# HG-Badge4.net
KiCad netlist of a schematic drawn in EAGLE
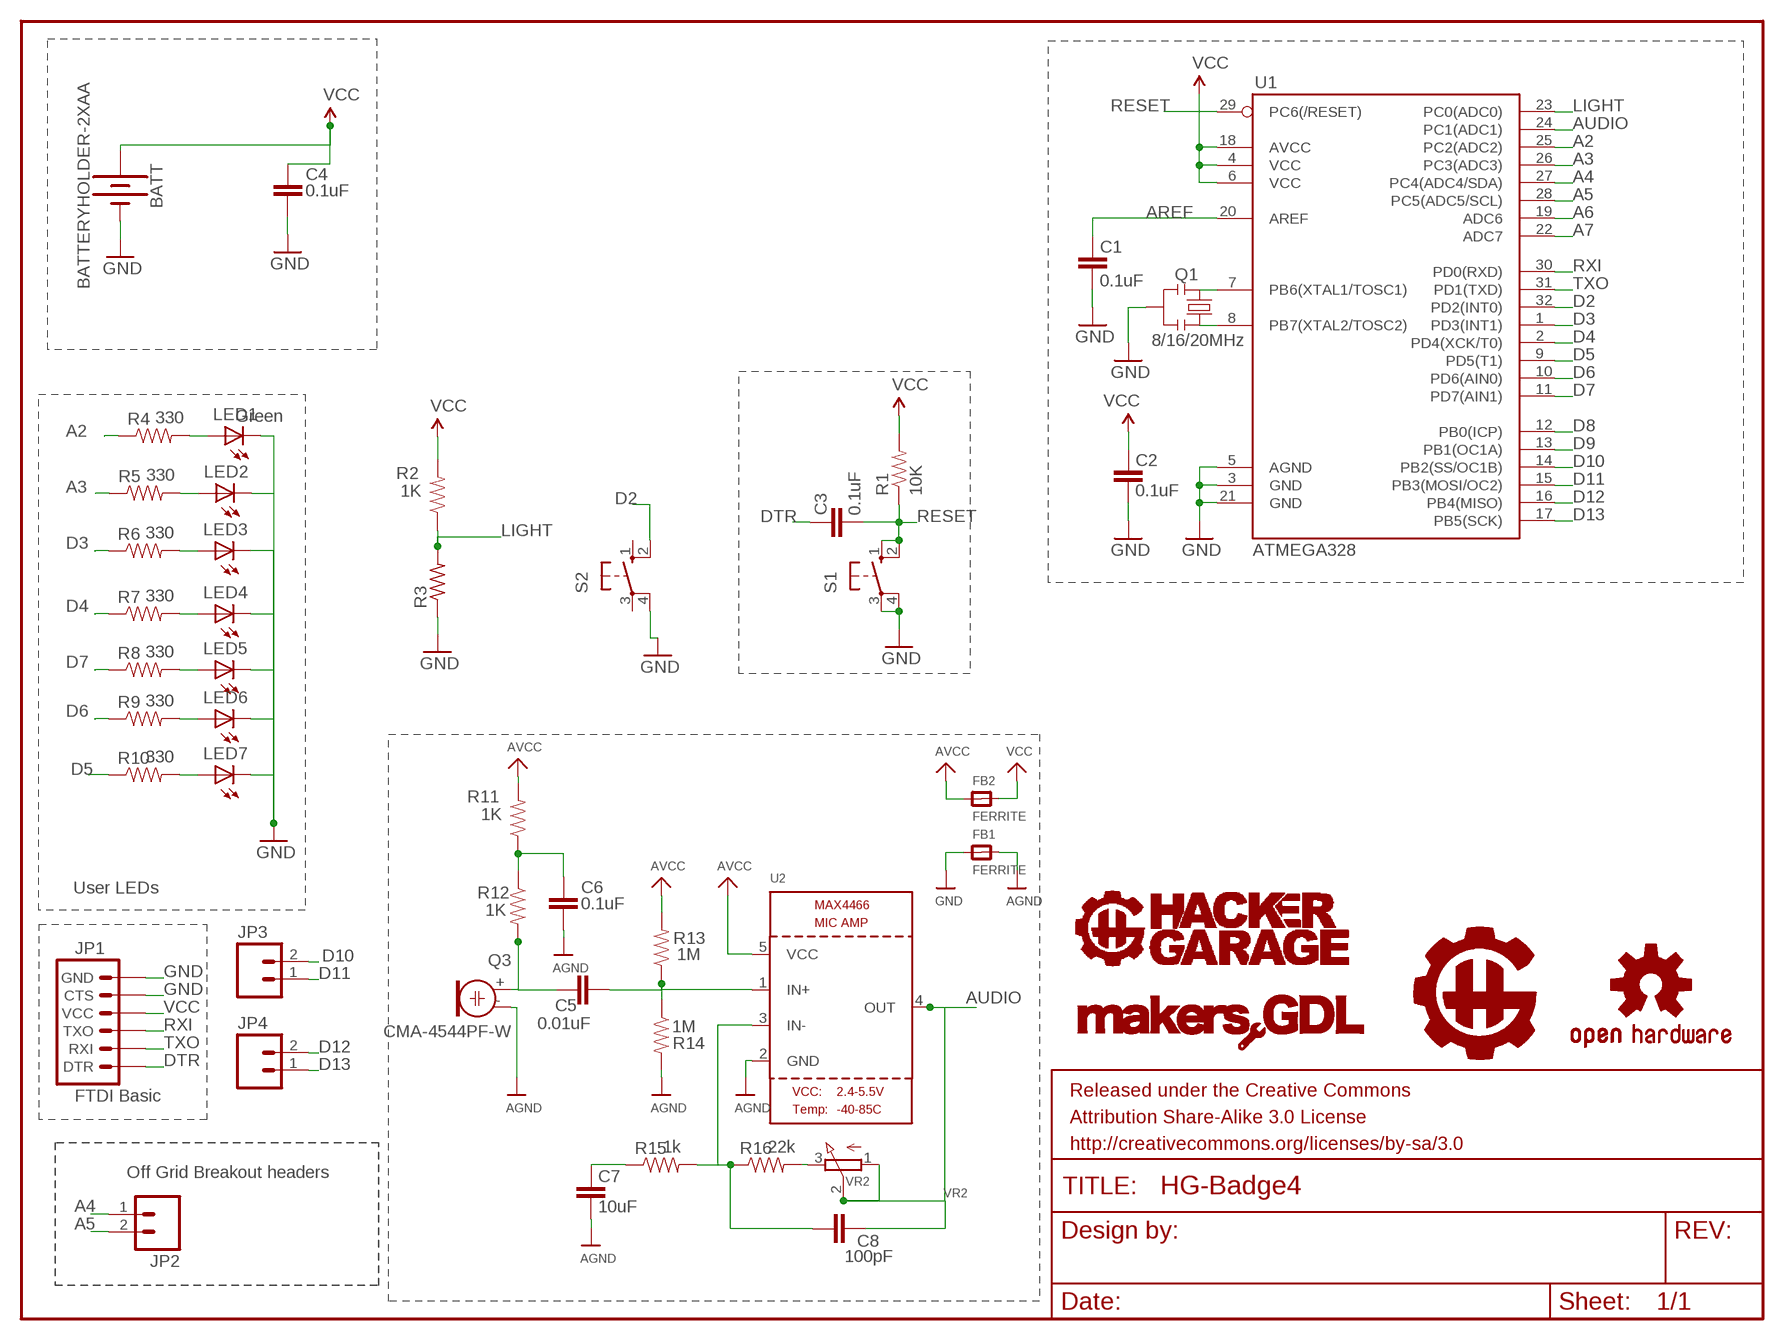
[diagram p0: schematic, sheet 1]

(export (version "E")
  (design (tool "Eeschema 10.0.6"))
  (components
    (comp (ref "BATT")
      (value "BATTERYHOLDER-2XAA")
      (footprint "eagle-import:BATT-HOLDER-2XAAA")
      (libsource (lib "eagle-import") (part "BATTERYHOLDER-2XAA"))
    )
    (comp (ref "C1")
      (value "0.1uF")
      (footprint "eagle-import:0603-CAP")
      (libsource (lib "eagle-import") (part "CAP0603-CAP"))
    )
    (comp (ref "C2")
      (value "0.1uF")
      (footprint "eagle-import:0603-CAP")
      (libsource (lib "eagle-import") (part "CAP0603-CAP"))
    )
    (comp (ref "C3")
      (value "0.1uF")
      (footprint "eagle-import:0603-CAP")
      (libsource (lib "eagle-import") (part "CAP0603-CAP"))
    )
    (comp (ref "C4")
      (value "0.1uF")
      (footprint "eagle-import:0603-CAP")
      (libsource (lib "eagle-import") (part "CAP0603-CAP"))
    )
    (comp (ref "C5")
      (value "0.01uF")
      (footprint "eagle-import:0603-CAP")
      (libsource (lib "eagle-import") (part "CAP0603-CAP"))
    )
    (comp (ref "C6")
      (value "0.1uF")
      (footprint "eagle-import:0603-CAP")
      (libsource (lib "eagle-import") (part "CAP0603-CAP"))
    )
    (comp (ref "C7")
      (value "10uF")
      (footprint "eagle-import:0603-CAP")
      (libsource (lib "eagle-import") (part "CAP0603-CAP"))
    )
    (comp (ref "C8")
      (value "100pF")
      (footprint "eagle-import:0603-CAP")
      (libsource (lib "eagle-import") (part "CAP0603-CAP"))
    )
    (comp (ref "FB1")
      (value "FERRITE")
      (footprint "eagle-import:0805")
      (libsource (lib "eagle-import") (part "FERRITE0805"))
    )
    (comp (ref "FB2")
      (value "FERRITE")
      (footprint "eagle-import:0805")
      (libsource (lib "eagle-import") (part "FERRITE0805"))
    )
    (comp (ref "FRAME1")
      (value "FRAME-LETTER")
      (footprint "eagle-import:CREATIVE_COMMONS")
      (libsource (lib "eagle-import") (part "FRAME-LETTER"))
    )
    (comp (ref "JP1")
      (value "FTDI Basic")
      (footprint "eagle-import:1X06")
      (libsource (lib "eagle-import") (part "ARDUINO_SERIAL_PROGRAMPTH"))
    )
    (comp (ref "JP2")
      (value "M02PTH")
      (footprint "eagle-import:1X02")
      (libsource (lib "eagle-import") (part "M02PTH"))
    )
    (comp (ref "JP3")
      (value "M02PTH")
      (footprint "eagle-import:1X02")
      (libsource (lib "eagle-import") (part "M02PTH"))
    )
    (comp (ref "JP4")
      (value "M02PTH")
      (footprint "eagle-import:1X02")
      (libsource (lib "eagle-import") (part "M02PTH"))
    )
    (comp (ref "LED1")
      (value "Green")
      (footprint "eagle-import:0603-LED-ALT1")
      (libsource (lib "eagle-import") (part "LED"))
    )
    (comp (ref "LED2")
      (value "Green")
      (footprint "eagle-import:0603-LED-ALT1")
      (libsource (lib "eagle-import") (part "LED"))
    )
    (comp (ref "LED3")
      (value "Green")
      (footprint "eagle-import:0603-LED-ALT1")
      (libsource (lib "eagle-import") (part "LED"))
    )
    (comp (ref "LED4")
      (value "Green")
      (footprint "eagle-import:0603-LED-ALT1")
      (libsource (lib "eagle-import") (part "LED"))
    )
    (comp (ref "LED5")
      (value "Green")
      (footprint "eagle-import:0603-LED-ALT1")
      (libsource (lib "eagle-import") (part "LED"))
    )
    (comp (ref "LED6")
      (value "Green")
      (footprint "eagle-import:0603-LED-ALT1")
      (libsource (lib "eagle-import") (part "LED"))
    )
    (comp (ref "LED7")
      (value "Green")
      (footprint "eagle-import:0603-LED-ALT1")
      (libsource (lib "eagle-import") (part "LED"))
    )
    (comp (ref "Q1")
      (value "8/16/20MHz")
      (footprint "eagle-import:RESONATOR-SMD-1_1")
      (libsource (lib "eagle-import") (part "RESONATOR1{colon}1"))
    )
    (comp (ref "Q3")
      (value "CMA-4544PF-W")
      (footprint "eagle-import:ELECTRET_9.7")
      (libsource (lib "eagle-import") (part "ELECTRET"))
    )
    (comp (ref "R1")
      (value "10K")
      (footprint "eagle-import:0603-RES")
      (libsource (lib "eagle-import") (part "RESISTOR0603-RES"))
    )
    (comp (ref "R2")
      (value "1K")
      (footprint "eagle-import:0603-RES")
      (libsource (lib "eagle-import") (part "RESISTOR0603-RES"))
    )
    (comp (ref "R3")
      (value "R-US_0204/2V")
      (footprint "eagle-import:0204V")
      (libsource (lib "eagle-import") (part "R-US_0204/2V"))
    )
    (comp (ref "R4")
      (value "330")
      (footprint "eagle-import:0603-RES")
      (libsource (lib "eagle-import") (part "RESISTOR0603-RES"))
    )
    (comp (ref "R5")
      (value "330")
      (footprint "eagle-import:0603-RES")
      (libsource (lib "eagle-import") (part "RESISTOR0603-RES"))
    )
    (comp (ref "R6")
      (value "330")
      (footprint "eagle-import:0603-RES")
      (libsource (lib "eagle-import") (part "RESISTOR0603-RES"))
    )
    (comp (ref "R7")
      (value "330")
      (footprint "eagle-import:0603-RES")
      (libsource (lib "eagle-import") (part "RESISTOR0603-RES"))
    )
    (comp (ref "R8")
      (value "330")
      (footprint "eagle-import:0603-RES")
      (libsource (lib "eagle-import") (part "RESISTOR0603-RES"))
    )
    (comp (ref "R9")
      (value "330")
      (footprint "eagle-import:0603-RES")
      (libsource (lib "eagle-import") (part "RESISTOR0603-RES"))
    )
    (comp (ref "R10")
      (value "330")
      (footprint "eagle-import:0603-RES")
      (libsource (lib "eagle-import") (part "RESISTOR0603-RES"))
    )
    (comp (ref "R11")
      (value "1K")
      (footprint "eagle-import:0603-RES")
      (libsource (lib "eagle-import") (part "RESISTOR0603-RES"))
    )
    (comp (ref "R12")
      (value "1K")
      (footprint "eagle-import:0603-RES")
      (libsource (lib "eagle-import") (part "RESISTOR0603-RES"))
    )
    (comp (ref "R13")
      (value "1M")
      (footprint "eagle-import:0603-RES")
      (libsource (lib "eagle-import") (part "RESISTOR0603-RES"))
    )
    (comp (ref "R14")
      (value "1M")
      (footprint "eagle-import:0603-RES")
      (libsource (lib "eagle-import") (part "RESISTOR0603-RES"))
    )
    (comp (ref "R15")
      (value "1k")
      (footprint "eagle-import:0603-RES")
      (libsource (lib "eagle-import") (part "RESISTOR0603-RES"))
    )
    (comp (ref "R16")
      (value "22k")
      (footprint "eagle-import:0603-RES")
      (libsource (lib "eagle-import") (part "RESISTOR0603-RES"))
    )
    (comp (ref "S1")
      (value "10-XX")
      (footprint "eagle-import:B3F-10XX")
      (fields (field (name "MPN") "B3F-1000"))
      (libsource (lib "eagle-import") (part "10-XX"))
    )
    (comp (ref "S2")
      (value "10-XX")
      (footprint "eagle-import:B3F-10XX")
      (fields (field (name "MPN") "B3F-1000"))
      (libsource (lib "eagle-import") (part "10-XX"))
    )
    (comp (ref "U$1")
      (value "HG-BADGE-FULL")
      (footprint "eagle-import:HG-BADGE")
      (libsource (lib "eagle-import") (part "HG-BADGE-FULL"))
    )
    (comp (ref "U$3")
      (value "OSHW-LOGOS")
      (footprint "eagle-import:OSHW-LOGO-S")
      (libsource (lib "eagle-import") (part "OSHW-LOGOS"))
    )
    (comp (ref "U$4")
      (value "MAKERSGDLLOGO-SMALL")
      (footprint "eagle-import:MAKERSGGL-SMALL")
      (libsource (lib "eagle-import") (part "MAKERSGDLLOGO-SMALL"))
    )
    (comp (ref "U$5")
      (value "HACKERGARAGEFULL")
      (footprint "eagle-import:HACKERGARAGEFULL-SMALL")
      (libsource (lib "eagle-import") (part "HACKERGARAGEFULL"))
    )
    (comp (ref "U1")
      (value "ATMEGA328")
      (footprint "eagle-import:TQFP32-08")
      (libsource (lib "eagle-import") (part "ATMEGA168"))
    )
    (comp (ref "U2")
      (value "MAX4466EXK+T")
      (footprint "eagle-import:SC70-5")
      (libsource (lib "eagle-import") (part "MAX4466{dblquote}{dblquote}"))
    )
    (comp (ref "VR2")
      (value "VR2")
      (footprint "eagle-import:TRIMPOT_BOURNS_TC33X-2")
      (libsource (lib "eagle-import") (part "TRIMPOTTC33X-2"))
    )
  )
  (nets
    (net (code "1") (name "/A2") (class "Default")
      (node (ref "R4") (pin "1") (pinfunction "1_1") (pintype "passive"))
      (node (ref "U1") (pin "25") (pinfunction "PC2(ADC2)_25") (pintype "bidirectional"))
    )
    (net (code "2") (name "/A3") (class "Default")
      (node (ref "R5") (pin "1") (pinfunction "1_1") (pintype "passive"))
      (node (ref "U1") (pin "26") (pinfunction "PC3(ADC3)_26") (pintype "bidirectional"))
    )
    (net (code "3") (name "/A4") (class "Default")
      (node (ref "JP2") (pin "1") (pinfunction "1_1") (pintype "passive"))
      (node (ref "U1") (pin "27") (pinfunction "PC4(ADC4/SDA)_27") (pintype "bidirectional"))
    )
    (net (code "4") (name "/A5") (class "Default")
      (node (ref "JP2") (pin "2") (pinfunction "2_2") (pintype "passive"))
      (node (ref "U1") (pin "28") (pinfunction "PC5(ADC5/SCL)_28") (pintype "bidirectional"))
    )
    (net (code "5") (name "/A6") (class "Default")
      (node (ref "U1") (pin "19") (pinfunction "ADC6_19") (pintype "bidirectional"))
    )
    (net (code "6") (name "/A7") (class "Default")
      (node (ref "U1") (pin "22") (pinfunction "ADC7_22") (pintype "bidirectional"))
    )
    (net (code "7") (name "/AREF") (class "Default")
      (node (ref "C1") (pin "2") (pinfunction "2_2") (pintype "passive"))
      (node (ref "U1") (pin "20") (pinfunction "AREF_20") (pintype "bidirectional"))
    )
    (net (code "8") (name "/AUDIO") (class "Default")
      (node (ref "C8") (pin "1") (pinfunction "1_1") (pintype "passive"))
      (node (ref "U1") (pin "24") (pinfunction "PC1(ADC1)_24") (pintype "bidirectional"))
      (node (ref "U2") (pin "4") (pinfunction "OUT_4") (pintype "bidirectional"))
      (node (ref "VR2") (pin "1") (pinfunction "A_1") (pintype "passive"))
      (node (ref "VR2") (pin "2") (pinfunction "S_2") (pintype "passive"))
    )
    (net (code "9") (name "/D2") (class "Default")
      (node (ref "S2") (pin "2") (pinfunction "S1_2") (pintype "passive"))
      (node (ref "U1") (pin "32") (pinfunction "PD2(INT0)_32") (pintype "bidirectional"))
    )
    (net (code "10") (name "/D3") (class "Default")
      (node (ref "R6") (pin "1") (pinfunction "1_1") (pintype "passive"))
      (node (ref "U1") (pin "1") (pinfunction "PD3(INT1)_1") (pintype "bidirectional"))
    )
    (net (code "11") (name "/D4") (class "Default")
      (node (ref "R7") (pin "1") (pinfunction "1_1") (pintype "passive"))
      (node (ref "U1") (pin "2") (pinfunction "PD4(XCK/T0)_2") (pintype "bidirectional"))
    )
    (net (code "12") (name "/D5") (class "Default")
      (node (ref "R10") (pin "1") (pinfunction "1_1") (pintype "passive"))
      (node (ref "U1") (pin "9") (pinfunction "PD5(T1)_9") (pintype "bidirectional"))
    )
    (net (code "13") (name "/D6") (class "Default")
      (node (ref "R9") (pin "1") (pinfunction "1_1") (pintype "passive"))
      (node (ref "U1") (pin "10") (pinfunction "PD6(AIN0)_10") (pintype "bidirectional"))
    )
    (net (code "14") (name "/D7") (class "Default")
      (node (ref "R8") (pin "1") (pinfunction "1_1") (pintype "passive"))
      (node (ref "U1") (pin "11") (pinfunction "PD7(AIN1)_11") (pintype "bidirectional"))
    )
    (net (code "15") (name "/D8") (class "Default")
      (node (ref "U1") (pin "12") (pinfunction "PB0(ICP)_12") (pintype "bidirectional"))
    )
    (net (code "16") (name "/D9") (class "Default")
      (node (ref "U1") (pin "13") (pinfunction "PB1(OC1A)_13") (pintype "bidirectional"))
    )
    (net (code "17") (name "/D10") (class "Default")
      (node (ref "JP3") (pin "2") (pinfunction "2_2") (pintype "passive"))
      (node (ref "U1") (pin "14") (pinfunction "PB2(SS/OC1B)_14") (pintype "bidirectional"))
    )
    (net (code "18") (name "/D11") (class "Default")
      (node (ref "JP3") (pin "1") (pinfunction "1_1") (pintype "passive"))
      (node (ref "U1") (pin "15") (pinfunction "PB3(MOSI/OC2)_15") (pintype "bidirectional"))
    )
    (net (code "19") (name "/D12") (class "Default")
      (node (ref "JP4") (pin "2") (pinfunction "2_2") (pintype "passive"))
      (node (ref "U1") (pin "16") (pinfunction "PB4(MISO)_16") (pintype "bidirectional"))
    )
    (net (code "20") (name "/D13") (class "Default")
      (node (ref "JP4") (pin "1") (pinfunction "1_1") (pintype "passive"))
      (node (ref "U1") (pin "17") (pinfunction "PB5(SCK)_17") (pintype "bidirectional"))
    )
    (net (code "21") (name "/DTR") (class "Default")
      (node (ref "C3") (pin "2") (pinfunction "2_2") (pintype "passive"))
      (node (ref "JP1") (pin "1") (pinfunction "DTR_1") (pintype "passive"))
    )
    (net (code "22") (name "/LIGHT") (class "Default")
      (node (ref "R2") (pin "1") (pinfunction "1_1") (pintype "passive"))
      (node (ref "R3") (pin "2") (pinfunction "2_2") (pintype "passive"))
      (node (ref "U1") (pin "23") (pinfunction "PC0(ADC0)_23") (pintype "bidirectional"))
    )
    (net (code "23") (name "/RESET") (class "Default")
      (node (ref "C3") (pin "1") (pinfunction "1_1") (pintype "passive"))
      (node (ref "R1") (pin "1") (pinfunction "1_1") (pintype "passive"))
      (node (ref "S1") (pin "1") (pinfunction "S_1") (pintype "passive"))
      (node (ref "S1") (pin "2") (pinfunction "S1_2") (pintype "passive"))
      (node (ref "U1") (pin "29") (pinfunction "PC6(/RESET)_29") (pintype "bidirectional"))
    )
    (net (code "24") (name "/RXI") (class "Default")
      (node (ref "JP1") (pin "3") (pinfunction "TXO_3") (pintype "passive"))
      (node (ref "U1") (pin "30") (pinfunction "PD0(RXD)_30") (pintype "bidirectional"))
    )
    (net (code "25") (name "/TXO") (class "Default")
      (node (ref "JP1") (pin "2") (pinfunction "RXI_2") (pintype "passive"))
      (node (ref "U1") (pin "31") (pinfunction "PD1(TXD)_31") (pintype "bidirectional"))
    )
    (net (code "26") (name "AGND") (class "Default")
      (node (ref "C6") (pin "1") (pinfunction "1_1") (pintype "passive"))
      (node (ref "C7") (pin "1") (pinfunction "1_1") (pintype "passive"))
      (node (ref "FB1") (pin "2") (pinfunction "P$2_2") (pintype "passive"))
      (node (ref "Q3") (pin "-") (pinfunction "1_-") (pintype "passive"))
      (node (ref "R14") (pin "2") (pinfunction "2_2") (pintype "passive"))
      (node (ref "U2") (pin "2") (pinfunction "GND_2") (pintype "bidirectional"))
    )
    (net (code "27") (name "AVCC") (class "Default")
      (node (ref "FB2") (pin "1") (pinfunction "P$1_1") (pintype "passive"))
      (node (ref "R11") (pin "2") (pinfunction "2_2") (pintype "passive"))
      (node (ref "R13") (pin "2") (pinfunction "2_2") (pintype "passive"))
      (node (ref "U2") (pin "5") (pinfunction "VCC_5") (pintype "bidirectional"))
    )
    (net (code "28") (name "GND") (class "Default")
      (node (ref "BATT") (pin "P$1") (pinfunction "-_P$1") (pintype "power_in"))
      (node (ref "C1") (pin "1") (pinfunction "1_1") (pintype "passive"))
      (node (ref "C2") (pin "1") (pinfunction "1_1") (pintype "passive"))
      (node (ref "C4") (pin "1") (pinfunction "1_1") (pintype "passive"))
      (node (ref "FB1") (pin "1") (pinfunction "P$1_1") (pintype "passive"))
      (node (ref "JP1") (pin "5") (pinfunction "CTS_5") (pintype "passive"))
      (node (ref "JP1") (pin "6") (pinfunction "GND_6") (pintype "passive"))
      (node (ref "LED1") (pin "C") (pinfunction "C_C") (pintype "passive"))
      (node (ref "LED3") (pin "C") (pinfunction "C_C") (pintype "passive"))
      (node (ref "LED4") (pin "C") (pinfunction "C_C") (pintype "passive"))
      (node (ref "LED5") (pin "C") (pinfunction "C_C") (pintype "passive"))
      (node (ref "LED6") (pin "C") (pinfunction "C_C") (pintype "passive"))
      (node (ref "LED7") (pin "C") (pinfunction "C_C") (pintype "passive"))
      (node (ref "Q1") (pin "2") (pinfunction "2_2") (pintype "passive"))
      (node (ref "R3") (pin "1") (pinfunction "1_1") (pintype "passive"))
      (node (ref "S1") (pin "3") (pinfunction "P_3") (pintype "passive"))
      (node (ref "S1") (pin "4") (pinfunction "P1_4") (pintype "passive"))
      (node (ref "S2") (pin "4") (pinfunction "P1_4") (pintype "passive"))
      (node (ref "U1") (pin "21") (pinfunction "GND_21") (pintype "bidirectional"))
      (node (ref "U1") (pin "3") (pinfunction "GND_3") (pintype "bidirectional"))
      (node (ref "U1") (pin "5") (pinfunction "AGND_5") (pintype "bidirectional"))
    )
    (net (code "29") (name "Net-(C6-Pad2)") (class "Default")
      (node (ref "C6") (pin "2") (pinfunction "2_2") (pintype "passive"))
      (node (ref "R11") (pin "1") (pinfunction "1_1") (pintype "passive"))
      (node (ref "R12") (pin "1") (pinfunction "1_1") (pintype "passive"))
    )
    (net (code "30") (name "Net-(C7-Pad2)") (class "Default")
      (node (ref "C7") (pin "2") (pinfunction "2_2") (pintype "passive"))
      (node (ref "R15") (pin "1") (pinfunction "1_1") (pintype "passive"))
    )
    (net (code "31") (name "Net-(LED1-PadA)") (class "Default")
      (node (ref "LED1") (pin "A") (pinfunction "A_A") (pintype "passive"))
      (node (ref "R4") (pin "2") (pinfunction "2_2") (pintype "passive"))
    )
    (net (code "32") (name "Net-(LED2-PadA)") (class "Default")
      (node (ref "LED2") (pin "A") (pinfunction "A_A") (pintype "passive"))
      (node (ref "R5") (pin "2") (pinfunction "2_2") (pintype "passive"))
    )
    (net (code "33") (name "Net-(LED3-PadA)") (class "Default")
      (node (ref "LED3") (pin "A") (pinfunction "A_A") (pintype "passive"))
      (node (ref "R6") (pin "2") (pinfunction "2_2") (pintype "passive"))
    )
    (net (code "34") (name "Net-(LED4-PadA)") (class "Default")
      (node (ref "LED4") (pin "A") (pinfunction "A_A") (pintype "passive"))
      (node (ref "R7") (pin "2") (pinfunction "2_2") (pintype "passive"))
    )
    (net (code "35") (name "Net-(LED5-PadA)") (class "Default")
      (node (ref "LED5") (pin "A") (pinfunction "A_A") (pintype "passive"))
      (node (ref "R8") (pin "2") (pinfunction "2_2") (pintype "passive"))
    )
    (net (code "36") (name "Net-(LED6-PadA)") (class "Default")
      (node (ref "LED6") (pin "A") (pinfunction "A_A") (pintype "passive"))
      (node (ref "R9") (pin "2") (pinfunction "2_2") (pintype "passive"))
    )
    (net (code "37") (name "Net-(LED7-PadA)") (class "Default")
      (node (ref "LED7") (pin "A") (pinfunction "A_A") (pintype "passive"))
      (node (ref "R10") (pin "2") (pinfunction "2_2") (pintype "passive"))
    )
    (net (code "38") (name "Net-(Q3-2)") (class "Default")
      (node (ref "C5") (pin "2") (pinfunction "2_2") (pintype "passive"))
      (node (ref "Q3") (pin "+") (pinfunction "2_+") (pintype "passive"))
      (node (ref "R12") (pin "2") (pinfunction "2_2") (pintype "passive"))
    )
    (net (code "39") (name "Net-(U1-PB6(XTAL1{slash}TOSC1))") (class "Default")
      (node (ref "Q1") (pin "1") (pinfunction "1_1") (pintype "passive"))
      (node (ref "U1") (pin "7") (pinfunction "PB6(XTAL1/TOSC1)_7") (pintype "bidirectional"))
    )
    (net (code "40") (name "Net-(U1-PB7(XTAL2{slash}TOSC2))") (class "Default")
      (node (ref "Q1") (pin "3") (pinfunction "3_3") (pintype "passive"))
      (node (ref "U1") (pin "8") (pinfunction "PB7(XTAL2/TOSC2)_8") (pintype "bidirectional"))
    )
    (net (code "41") (name "Net-(U2-IN+)") (class "Default")
      (node (ref "C5") (pin "1") (pinfunction "1_1") (pintype "passive"))
      (node (ref "R13") (pin "1") (pinfunction "1_1") (pintype "passive"))
      (node (ref "R14") (pin "1") (pinfunction "1_1") (pintype "passive"))
      (node (ref "U2") (pin "1") (pinfunction "IN+_1") (pintype "bidirectional"))
    )
    (net (code "42") (name "Net-(U2-IN-)") (class "Default")
      (node (ref "C8") (pin "2") (pinfunction "2_2") (pintype "passive"))
      (node (ref "R15") (pin "2") (pinfunction "2_2") (pintype "passive"))
      (node (ref "R16") (pin "1") (pinfunction "1_1") (pintype "passive"))
      (node (ref "U2") (pin "3") (pinfunction "IN-_3") (pintype "bidirectional"))
    )
    (net (code "43") (name "Net-(VR2-E)") (class "Default")
      (node (ref "R16") (pin "2") (pinfunction "2_2") (pintype "passive"))
      (node (ref "VR2") (pin "3") (pinfunction "E_3") (pintype "passive"))
    )
    (net (code "44") (name "VCC") (class "Default")
      (node (ref "BATT") (pin "P$2") (pinfunction "+_P$2") (pintype "power_in"))
      (node (ref "C2") (pin "2") (pinfunction "2_2") (pintype "passive"))
      (node (ref "C4") (pin "2") (pinfunction "2_2") (pintype "passive"))
      (node (ref "FB2") (pin "2") (pinfunction "P$2_2") (pintype "passive"))
      (node (ref "JP1") (pin "4") (pinfunction "VCC_4") (pintype "passive"))
      (node (ref "R1") (pin "2") (pinfunction "2_2") (pintype "passive"))
      (node (ref "R2") (pin "2") (pinfunction "2_2") (pintype "passive"))
      (node (ref "U1") (pin "18") (pinfunction "AVCC_18") (pintype "bidirectional"))
      (node (ref "U1") (pin "4") (pinfunction "VCC_4") (pintype "bidirectional"))
      (node (ref "U1") (pin "6") (pinfunction "VCC_6") (pintype "bidirectional"))
    )
    (net (code "45") (name "unconnected-(LED2-PadC)") (class "Default")
      (node (ref "LED2") (pin "C") (pinfunction "C_C") (pintype "passive"))
    )
    (net (code "46") (name "unconnected-(S2-P-Pad3)") (class "Default")
      (node (ref "S2") (pin "3") (pinfunction "P_3") (pintype "passive"))
    )
    (net (code "47") (name "unconnected-(S2-S-Pad1)") (class "Default")
      (node (ref "S2") (pin "1") (pinfunction "S_1") (pintype "passive"))
    )
  )
)
